# sensor.net
KiCad netlist of a schematic drawn in Altium Designer
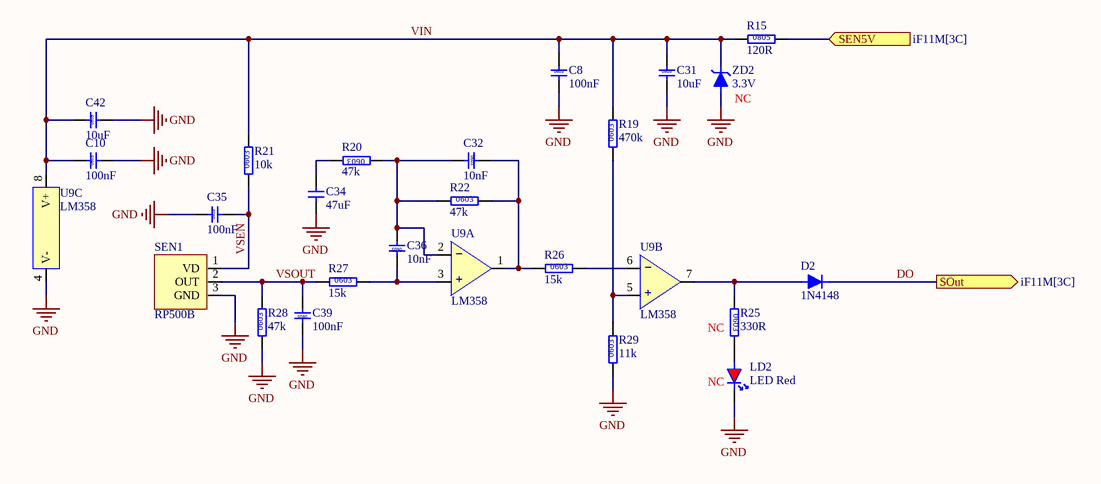
[diagram p0: sensor.SchDoc]

(export (version "E")
  (design (tool "Eeschema 10.0.6"))
  (components
    (comp (ref "C8")
      (value "100nF")
      (footprint "C0603")
      (description "10% 50V")
      (fields (field (name "PART NO") "W-T-CA-X703N100K50VNT") (field (name "MANUFACTURER") "FENGHUA"))
      (libsource (lib "Rescap") (part "C 0603 100nF 50V"))
    )
    (comp (ref "C10")
      (value "100nF")
      (footprint "C0603")
      (description "10% 50V")
      (fields (field (name "PART NO") "W-T-CA-X703N100K50VNT") (field (name "MANUFACTURER") "FENGHUA"))
      (libsource (lib "Rescap") (part "C 0603 100nF 50V"))
    )
    (comp (ref "C31")
      (value "10uF")
      (footprint "C0805")
      (description "10% 25V")
      (fields (field (name "PART NO") "WP0005368"))
      (libsource (lib "Rescap") (part "C 0805 10uF 25V"))
    )
    (comp (ref "C32")
      (value "10nF")
      (footprint "C0603")
      (description "10% 50V")
      (fields (field (name "PART NO") "W-T-CA-X703N10K50VNT"))
      (libsource (lib "Rescap") (part "C 0603 10nF 50V"))
    )
    (comp (ref "C34")
      (value "47uF")
      (footprint "C0603")
      (description "SMD resistor  Package")
      (libsource (lib "Capacitors") (part "Capacitor"))
    )
    (comp (ref "C35")
      (value "100nF")
      (footprint "C0805")
      (description "10% 50V")
      (fields (field (name "PART NO") "W-T-CA-X705N100K50VNT"))
      (libsource (lib "Rescap") (part "C 0805 100nF 50V"))
    )
    (comp (ref "C36")
      (value "10nF")
      (footprint "C0603")
      (description "10% 50V")
      (fields (field (name "PART NO") "W-T-CA-X703N10K50VNT"))
      (libsource (lib "Rescap") (part "C 0603 10nF 50V"))
    )
    (comp (ref "C39")
      (value "100nF")
      (footprint "C0805")
      (description "10% 50V")
      (fields (field (name "PART NO") "W-T-CA-X705N100K50VNT"))
      (libsource (lib "Rescap") (part "C 0805 100nF 50V"))
    )
    (comp (ref "C42")
      (value "10uF")
      (footprint "C0805")
      (description "10% 25V")
      (fields (field (name "PART NO") "WP0005368"))
      (libsource (lib "Rescap") (part "C 0805 10uF 25V"))
    )
    (comp (ref "D2")
      (value "1N4148")
      (footprint "SOD-323")
      (fields (field (name "PART NO") "W-T-DE-1N4148-SOD123"))
      (libsource (lib "Rectifier") (part "IN4148"))
    )
    (comp (ref "LD2")
      (value "LED Red")
      (footprint "LED-0603-RED")
      (libsource (lib "Optoelectronics") (part "LED Red"))
    )
    (comp (ref "R15")
      (value "120R")
      (footprint "R0805-LD")
      (description "5%")
      (fields (field (name "PART NO") "W-T-RE-RS05K121JT"))
      (libsource (lib "Rescap") (part "R 0805 120R"))
    )
    (comp (ref "R19")
      (value "470k")
      (footprint "R0603-LD")
      (description "5%")
      (fields (field (name "PART NO") "W-T-RE-RS03K153JT") (field (name "MANUFACTURER") "改善传感器，2023/01/08新增"))
      (libsource (lib "Rescap") (part "R 0603 15k"))
    )
    (comp (ref "R20")
      (value "47k")
      (footprint "R0603-LD")
      (description "5%")
      (fields (field (name "PART NO") "W-T-RE-RS03K473JT"))
      (libsource (lib "Rescap") (part "R 0603 47k"))
    )
    (comp (ref "R21")
      (value "10k")
      (footprint "R0603-LD")
      (description "5%")
      (fields (field (name "PART NO") "W-T-RE-RS03K103JT") (field (name "MANUFACTURER") "热敏D541V11增加1颗用量"))
      (libsource (lib "Rescap") (part "R 0603 10k"))
    )
    (comp (ref "R22")
      (value "47k")
      (footprint "R0603-LD")
      (description "5%")
      (fields (field (name "PART NO") "W-T-RE-RS03K473JT"))
      (libsource (lib "Rescap") (part "R 0603 47k"))
    )
    (comp (ref "R25")
      (value "330R")
      (footprint "R0603-LD")
      (description "5%")
      (fields (field (name "PART NO") "W-T-RE-RS03K331JT"))
      (libsource (lib "Rescap") (part "R 0603 330R"))
    )
    (comp (ref "R26")
      (value "15k")
      (footprint "R0603-LD")
      (description "5%")
      (fields (field (name "PART NO") "W-T-RE-RS03K153JT") (field (name "MANUFACTURER") "改善传感器，2023/01/08新增"))
      (libsource (lib "Rescap") (part "R 0603 15k"))
    )
    (comp (ref "R27")
      (value "15k")
      (footprint "R0603-LD")
      (description "5%")
      (fields (field (name "PART NO") "W-T-RE-RS03K153JT") (field (name "MANUFACTURER") "改善传感器，2023/01/08新增"))
      (libsource (lib "Rescap") (part "R 0603 15k"))
    )
    (comp (ref "R28")
      (value "47k")
      (footprint "R0603-LD")
      (description "5%")
      (fields (field (name "PART NO") "W-T-RE-RS03K473JT"))
      (libsource (lib "Rescap") (part "R 0603 47k"))
    )
    (comp (ref "R29")
      (value "11k")
      (footprint "R0603-LD")
      (description "5%")
      (fields (field (name "PART NO") "W-T-RE-RS03K103JT") (field (name "MANUFACTURER") "热敏D541V11增加1颗用量"))
      (libsource (lib "Rescap") (part "R 0603 10k"))
    )
    (comp (ref "SEN1") (value "RP500B") (footprint "TO-5-Lbent") (libsource (lib "Sensor") (part "RP500B")))
    (comp (ref "U9")
      (value "LM358")
      (footprint "LM358-SOIC8")
      (description "DUAL OPAMP")
      (libsource (lib "mylib2") (part "LM358"))
    )
    (comp (ref "ZD2")
      (value "3.3V")
      (footprint "SOD-323")
      (description "Zener Diode 300mW")
      (libsource (lib "Rectifier") (part "Zener Diode"))
    )
  )
  (nets
    (net (code "1") (name "/DO") (class "Default")
      (node (ref "D2") (pin "2") (pinfunction "K_2") (pintype "passive"))
    )
    (net (code "2") (name "/SEN5V") (class "Default")
      (node (ref "R15") (pin "2") (pinfunction "2_2") (pintype "passive"))
    )
    (net (code "3") (name "/VIN") (class "Default")
      (node (ref "C10") (pin "1") (pinfunction "1_1") (pintype "passive"))
      (node (ref "C31") (pin "1") (pinfunction "1_1") (pintype "passive"))
      (node (ref "C42") (pin "1") (pinfunction "1_1") (pintype "passive"))
      (node (ref "C8") (pin "1") (pinfunction "1_1") (pintype "passive"))
      (node (ref "R15") (pin "1") (pinfunction "1_1") (pintype "passive"))
      (node (ref "R19") (pin "2") (pinfunction "2_2") (pintype "passive"))
      (node (ref "R21") (pin "2") (pinfunction "2_2") (pintype "passive"))
      (node (ref "U9") (pin "8") (pinfunction "V+_8") (pintype "passive"))
      (node (ref "ZD2") (pin "2") (pinfunction "K_2") (pintype "passive"))
    )
    (net (code "4") (name "/VSEN") (class "Default")
      (node (ref "C35") (pin "2") (pinfunction "2_2") (pintype "passive"))
      (node (ref "R21") (pin "1") (pinfunction "1_1") (pintype "passive"))
      (node (ref "SEN1") (pin "1") (pinfunction "VD_1") (pintype "passive"))
    )
    (net (code "5") (name "/VSOUT") (class "Default")
      (node (ref "C39") (pin "2") (pinfunction "2_2") (pintype "passive"))
      (node (ref "R27") (pin "1") (pinfunction "1_1") (pintype "passive"))
      (node (ref "R28") (pin "2") (pinfunction "2_2") (pintype "passive"))
      (node (ref "SEN1") (pin "2") (pinfunction "OUT_2") (pintype "passive"))
    )
    (net (code "6") (name "GND") (class "Default")
      (node (ref "C10") (pin "2") (pinfunction "2_2") (pintype "passive"))
      (node (ref "C31") (pin "2") (pinfunction "2_2") (pintype "passive"))
      (node (ref "C34") (pin "2") (pinfunction "2_2") (pintype "passive"))
      (node (ref "C35") (pin "1") (pinfunction "1_1") (pintype "passive"))
      (node (ref "C39") (pin "1") (pinfunction "1_1") (pintype "passive"))
      (node (ref "C42") (pin "2") (pinfunction "2_2") (pintype "passive"))
      (node (ref "C8") (pin "2") (pinfunction "2_2") (pintype "passive"))
      (node (ref "LD2") (pin "2") (pinfunction "K_2") (pintype "passive"))
      (node (ref "R28") (pin "1") (pinfunction "1_1") (pintype "passive"))
      (node (ref "R29") (pin "1") (pinfunction "1_1") (pintype "passive"))
      (node (ref "SEN1") (pin "3") (pinfunction "GND_3") (pintype "passive"))
      (node (ref "U9") (pin "4") (pinfunction "V-_4") (pintype "passive"))
      (node (ref "ZD2") (pin "1") (pinfunction "A_1") (pintype "passive"))
    )
    (net (code "7") (name "Net-(C34-Pad1)") (class "Default")
      (node (ref "C34") (pin "1") (pinfunction "1_1") (pintype "passive"))
      (node (ref "R20") (pin "2") (pinfunction "2_2") (pintype "passive"))
    )
    (net (code "8") (name "Net-(D2-A)") (class "Default")
      (node (ref "D2") (pin "1") (pinfunction "A_1") (pintype "passive"))
      (node (ref "R25") (pin "1") (pinfunction "1_1") (pintype "passive"))
      (node (ref "U9") (pin "7") (pinfunction "O2_7") (pintype "passive"))
    )
    (net (code "9") (name "Net-(LD2-A)") (class "Default")
      (node (ref "LD2") (pin "1") (pinfunction "A_1") (pintype "passive"))
      (node (ref "R25") (pin "2") (pinfunction "2_2") (pintype "passive"))
    )
    (net (code "10") (name "Net-(U9A-+)") (class "Default")
      (node (ref "C36") (pin "1") (pinfunction "1_1") (pintype "passive"))
      (node (ref "R27") (pin "2") (pinfunction "2_2") (pintype "passive"))
      (node (ref "U9") (pin "3") (pinfunction "+_3") (pintype "passive"))
    )
    (net (code "11") (name "Net-(U9A--)") (class "Default")
      (node (ref "C32") (pin "2") (pinfunction "2_2") (pintype "passive"))
      (node (ref "C36") (pin "2") (pinfunction "2_2") (pintype "passive"))
      (node (ref "R20") (pin "1") (pinfunction "1_1") (pintype "passive"))
      (node (ref "R22") (pin "1") (pinfunction "1_1") (pintype "passive"))
      (node (ref "U9") (pin "2") (pinfunction "-_2") (pintype "passive"))
    )
    (net (code "12") (name "Net-(U9A-O1)") (class "Default")
      (node (ref "C32") (pin "1") (pinfunction "1_1") (pintype "passive"))
      (node (ref "R22") (pin "2") (pinfunction "2_2") (pintype "passive"))
      (node (ref "R26") (pin "1") (pinfunction "1_1") (pintype "passive"))
      (node (ref "U9") (pin "1") (pinfunction "O1_1") (pintype "passive"))
    )
    (net (code "13") (name "Net-(U9B-+)") (class "Default")
      (node (ref "R19") (pin "1") (pinfunction "1_1") (pintype "passive"))
      (node (ref "R29") (pin "2") (pinfunction "2_2") (pintype "passive"))
      (node (ref "U9") (pin "5") (pinfunction "+_5") (pintype "passive"))
    )
    (net (code "14") (name "Net-(U9B--)") (class "Default")
      (node (ref "R26") (pin "2") (pinfunction "2_2") (pintype "passive"))
      (node (ref "U9") (pin "6") (pinfunction "-_6") (pintype "passive"))
    )
  )
)
